# labwiz-module_servo_dual.net
KiCad netlist of a schematic drawn in EAGLE
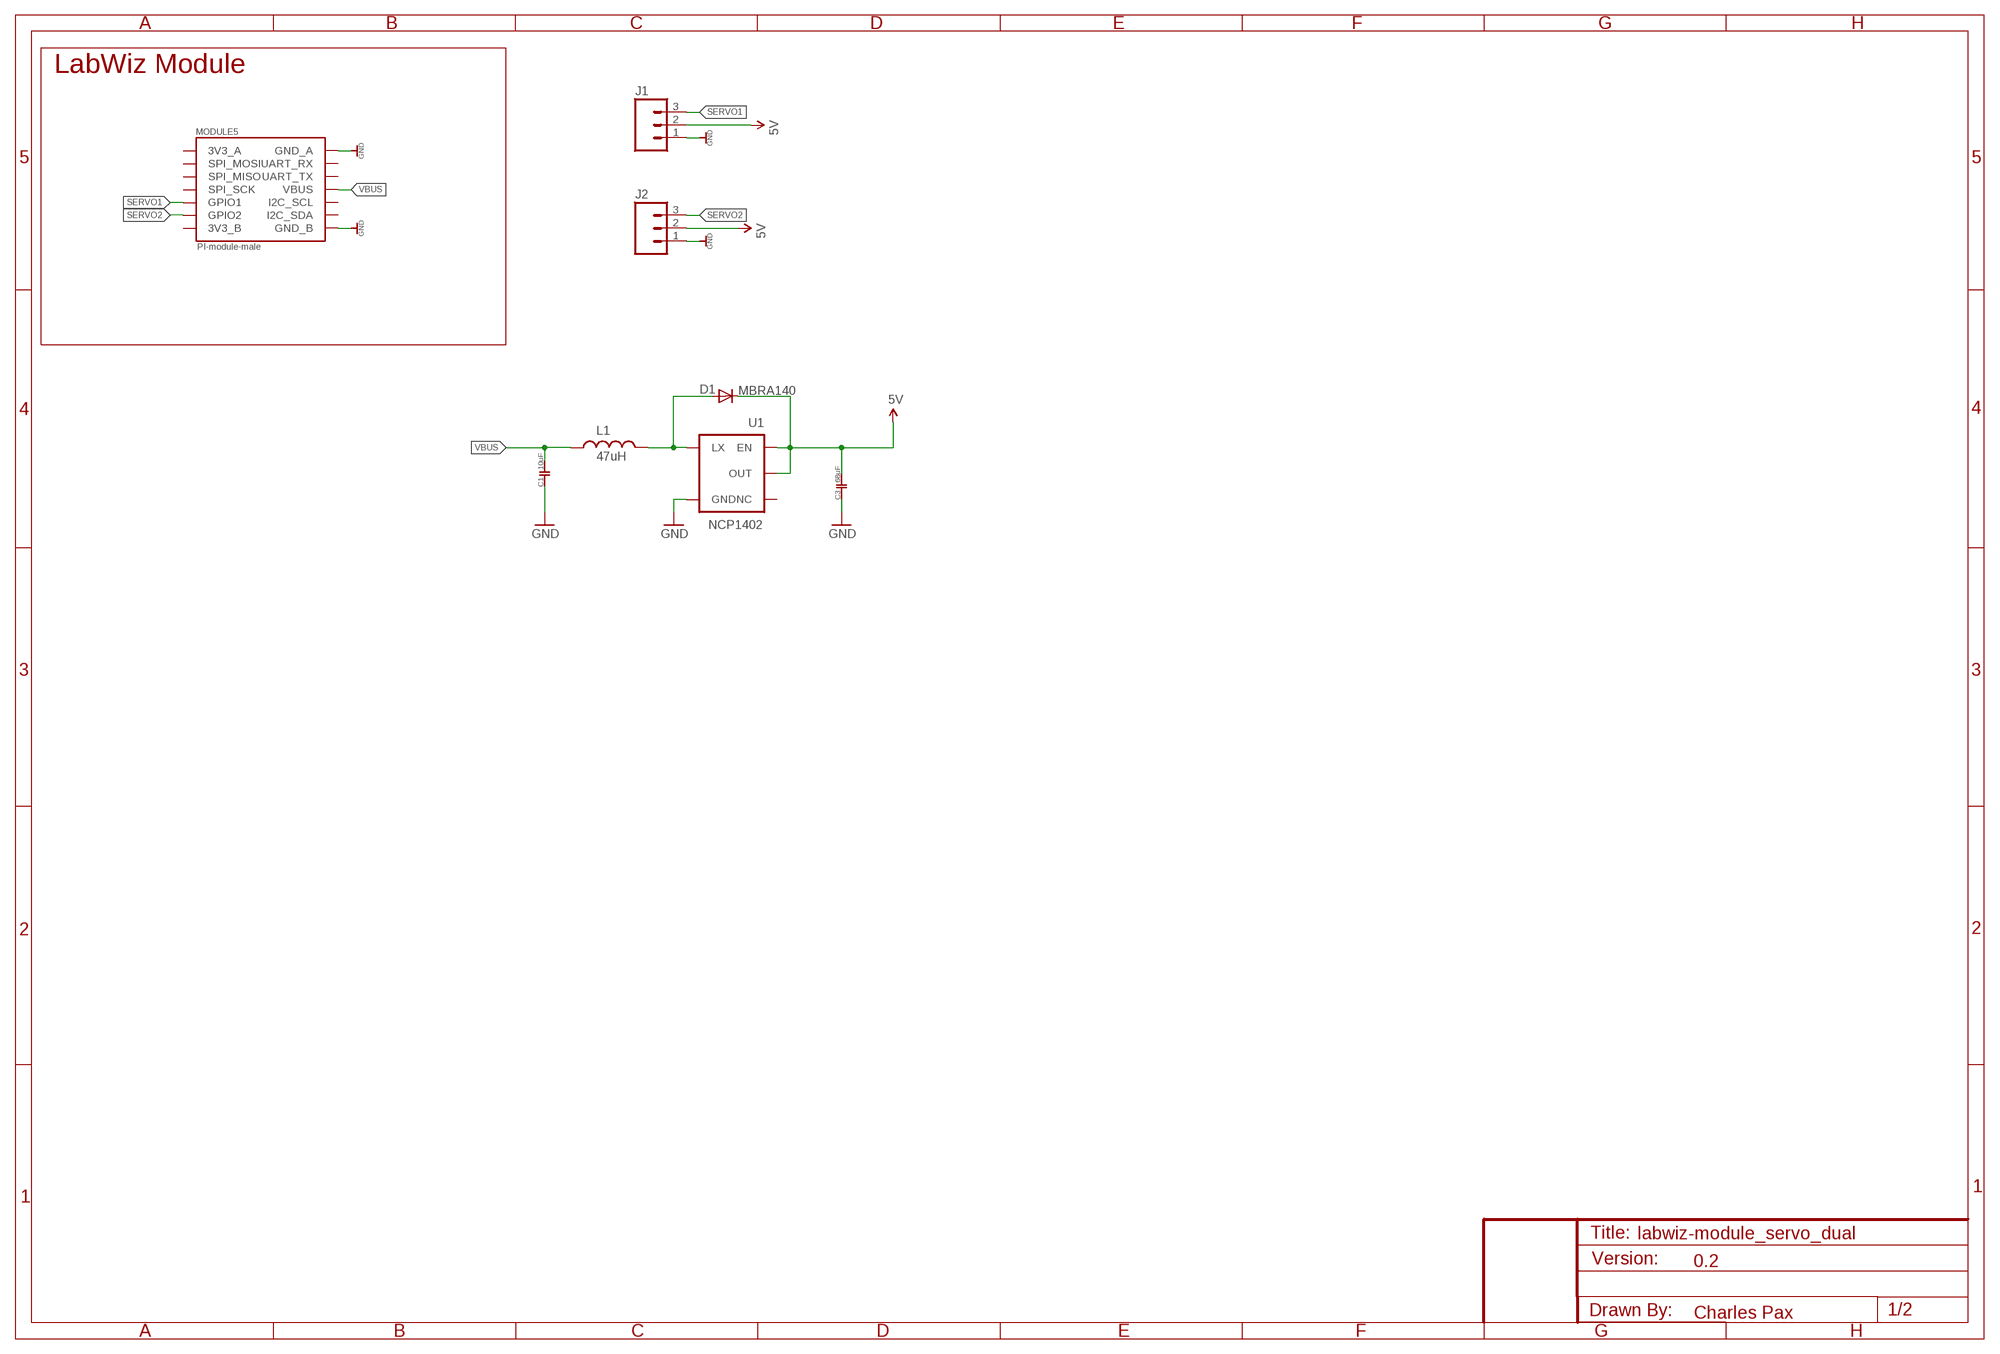
[diagram p0: schematic, sheet 1]

(export (version "E")
  (design (tool "Eeschema 10.0.6"))
  (components
    (comp (ref "C1")
      (value "10uF")
      (footprint "eagle-import:0603")
      (libsource (lib "eagle-import") (part "CAPACITOR_FIXED_0603_10UF"))
    )
    (comp (ref "C3")
      (value "68uF")
      (footprint "eagle-import:0603")
      (libsource (lib "eagle-import") (part "CAPACITOR_FIXED_0603"))
    )
    (comp (ref "D1")
      (value "MBRA140")
      (footprint "eagle-import:SMA-DIODE")
      (libsource (lib "eagle-import") (part "DIODESMA"))
    )
    (comp (ref "J1")
      (value "M031X03_SMD_RA_MALE_POST_SMALLEST")
      (footprint "eagle-import:1X03_SMD_RA_MALE_POST_SMALLEST")
      (libsource (lib "eagle-import") (part "M031X03_SMD_RA_MALE_POST_SMALLEST"))
    )
    (comp (ref "J2")
      (value "M031X03_SMD_RA_MALE_POST_SMALLEST")
      (footprint "eagle-import:1X03_SMD_RA_MALE_POST_SMALLEST")
      (libsource (lib "eagle-import") (part "M031X03_SMD_RA_MALE_POST_SMALLEST"))
    )
    (comp (ref "L1")
      (value "47uH")
      (footprint "eagle-import:CR54")
      (libsource (lib "eagle-import") (part "INDUCTORCR54"))
    )
    (comp (ref "MODULE5")
      (value "PI-module-male")
      (footprint "eagle-import:M07X2_2MM_EDGE")
      (fields (field (name "MF") "Pax Instruments") (field (name "MPN") "PIxxxx"))
      (libsource (lib "eagle-import") (part "PAX_MODULE_EDGE_MALE_MODULE"))
    )
    (comp (ref "U1")
      (value "NCP1402")
      (footprint "eagle-import:SOT23-5")
      (libsource (lib "eagle-import") (part "V_REG_NCP1400SOT23-5"))
    )
  )
  (nets
    (net (code "1") (name "3V3_A") (class "Default")
      (node (ref "MODULE5") (pin "P$13") (pinfunction "3V3_A_P$13") (pintype "power_in"))
    )
    (net (code "2") (name "5V") (class "Default")
      (node (ref "C3") (pin "2") (pinfunction "2_2") (pintype "passive"))
      (node (ref "D1") (pin "C") (pinfunction "C_C") (pintype "passive"))
      (node (ref "J1") (pin "2") (pinfunction "2_2") (pintype "passive"))
      (node (ref "J2") (pin "2") (pinfunction "2_2") (pintype "passive"))
      (node (ref "U1") (pin "1") (pinfunction "EN_1") (pintype "input"))
      (node (ref "U1") (pin "2") (pinfunction "OUT_2") (pintype "passive"))
    )
    (net (code "3") (name "GND") (class "Default")
      (node (ref "C1") (pin "1") (pinfunction "1_1") (pintype "passive"))
      (node (ref "C3") (pin "1") (pinfunction "1_1") (pintype "passive"))
      (node (ref "J1") (pin "1") (pinfunction "1_1") (pintype "passive"))
      (node (ref "J2") (pin "1") (pinfunction "1_1") (pintype "passive"))
      (node (ref "MODULE5") (pin "P$14") (pinfunction "GND_A_P$14") (pintype "power_in"))
      (node (ref "MODULE5") (pin "P$2") (pinfunction "GND_B_P$2") (pintype "bidirectional"))
      (node (ref "U1") (pin "4") (pinfunction "GND_4") (pintype "input"))
    )
    (net (code "4") (name "Net-(L1-2)") (class "Default")
      (node (ref "D1") (pin "A") (pinfunction "A_A") (pintype "passive"))
      (node (ref "L1") (pin "P$2") (pinfunction "2_P$2") (pintype "passive"))
      (node (ref "U1") (pin "5") (pinfunction "LX_5") (pintype "input"))
    )
    (net (code "5") (name "SERVO1") (class "Default")
      (node (ref "J1") (pin "3") (pinfunction "3_3") (pintype "passive"))
      (node (ref "MODULE5") (pin "P$5") (pinfunction "GPIO1_P$5") (pintype "bidirectional"))
    )
    (net (code "6") (name "SERVO2") (class "Default")
      (node (ref "J2") (pin "3") (pinfunction "3_3") (pintype "passive"))
      (node (ref "MODULE5") (pin "P$3") (pinfunction "GPIO2_P$3") (pintype "bidirectional"))
    )
    (net (code "7") (name "VBUS") (class "Default")
      (node (ref "C1") (pin "2") (pinfunction "2_2") (pintype "passive"))
      (node (ref "L1") (pin "P$1") (pinfunction "1_P$1") (pintype "passive"))
      (node (ref "MODULE5") (pin "P$8") (pinfunction "VBUS_P$8") (pintype "bidirectional"))
    )
    (net (code "8") (name "unconnected-(MODULE5-3V3_B-PadP$1)") (class "Default")
      (node (ref "MODULE5") (pin "P$1") (pinfunction "3V3_B_P$1") (pintype "bidirectional"))
    )
    (net (code "9") (name "unconnected-(MODULE5-I2C_SCL-PadP$6)") (class "Default")
      (node (ref "MODULE5") (pin "P$6") (pinfunction "I2C_SCL_P$6") (pintype "bidirectional"))
    )
    (net (code "10") (name "unconnected-(MODULE5-I2C_SDA-PadP$4)") (class "Default")
      (node (ref "MODULE5") (pin "P$4") (pinfunction "I2C_SDA_P$4") (pintype "bidirectional"))
    )
    (net (code "11") (name "unconnected-(MODULE5-SPI_MISO-PadP$9)") (class "Default")
      (node (ref "MODULE5") (pin "P$9") (pinfunction "SPI_MISO_P$9") (pintype "bidirectional"))
    )
    (net (code "12") (name "unconnected-(MODULE5-SPI_MOSI-PadP$11)") (class "Default")
      (node (ref "MODULE5") (pin "P$11") (pinfunction "SPI_MOSI_P$11") (pintype "bidirectional"))
    )
    (net (code "13") (name "unconnected-(MODULE5-SPI_SCK-PadP$7)") (class "Default")
      (node (ref "MODULE5") (pin "P$7") (pinfunction "SPI_SCK_P$7") (pintype "bidirectional"))
    )
    (net (code "14") (name "unconnected-(MODULE5-UART_RX-PadP$12)") (class "Default")
      (node (ref "MODULE5") (pin "P$12") (pinfunction "UART_RX_P$12") (pintype "bidirectional"))
    )
    (net (code "15") (name "unconnected-(MODULE5-UART_TX-PadP$10)") (class "Default")
      (node (ref "MODULE5") (pin "P$10") (pinfunction "UART_TX_P$10") (pintype "bidirectional"))
    )
    (net (code "16") (name "unconnected-(U1-NC-Pad3)") (class "Default")
      (node (ref "U1") (pin "3") (pinfunction "NC_3") (pintype "input"))
    )
  )
)
